# BluePill.net
KiCad netlist of a schematic drawn in Altium Designer
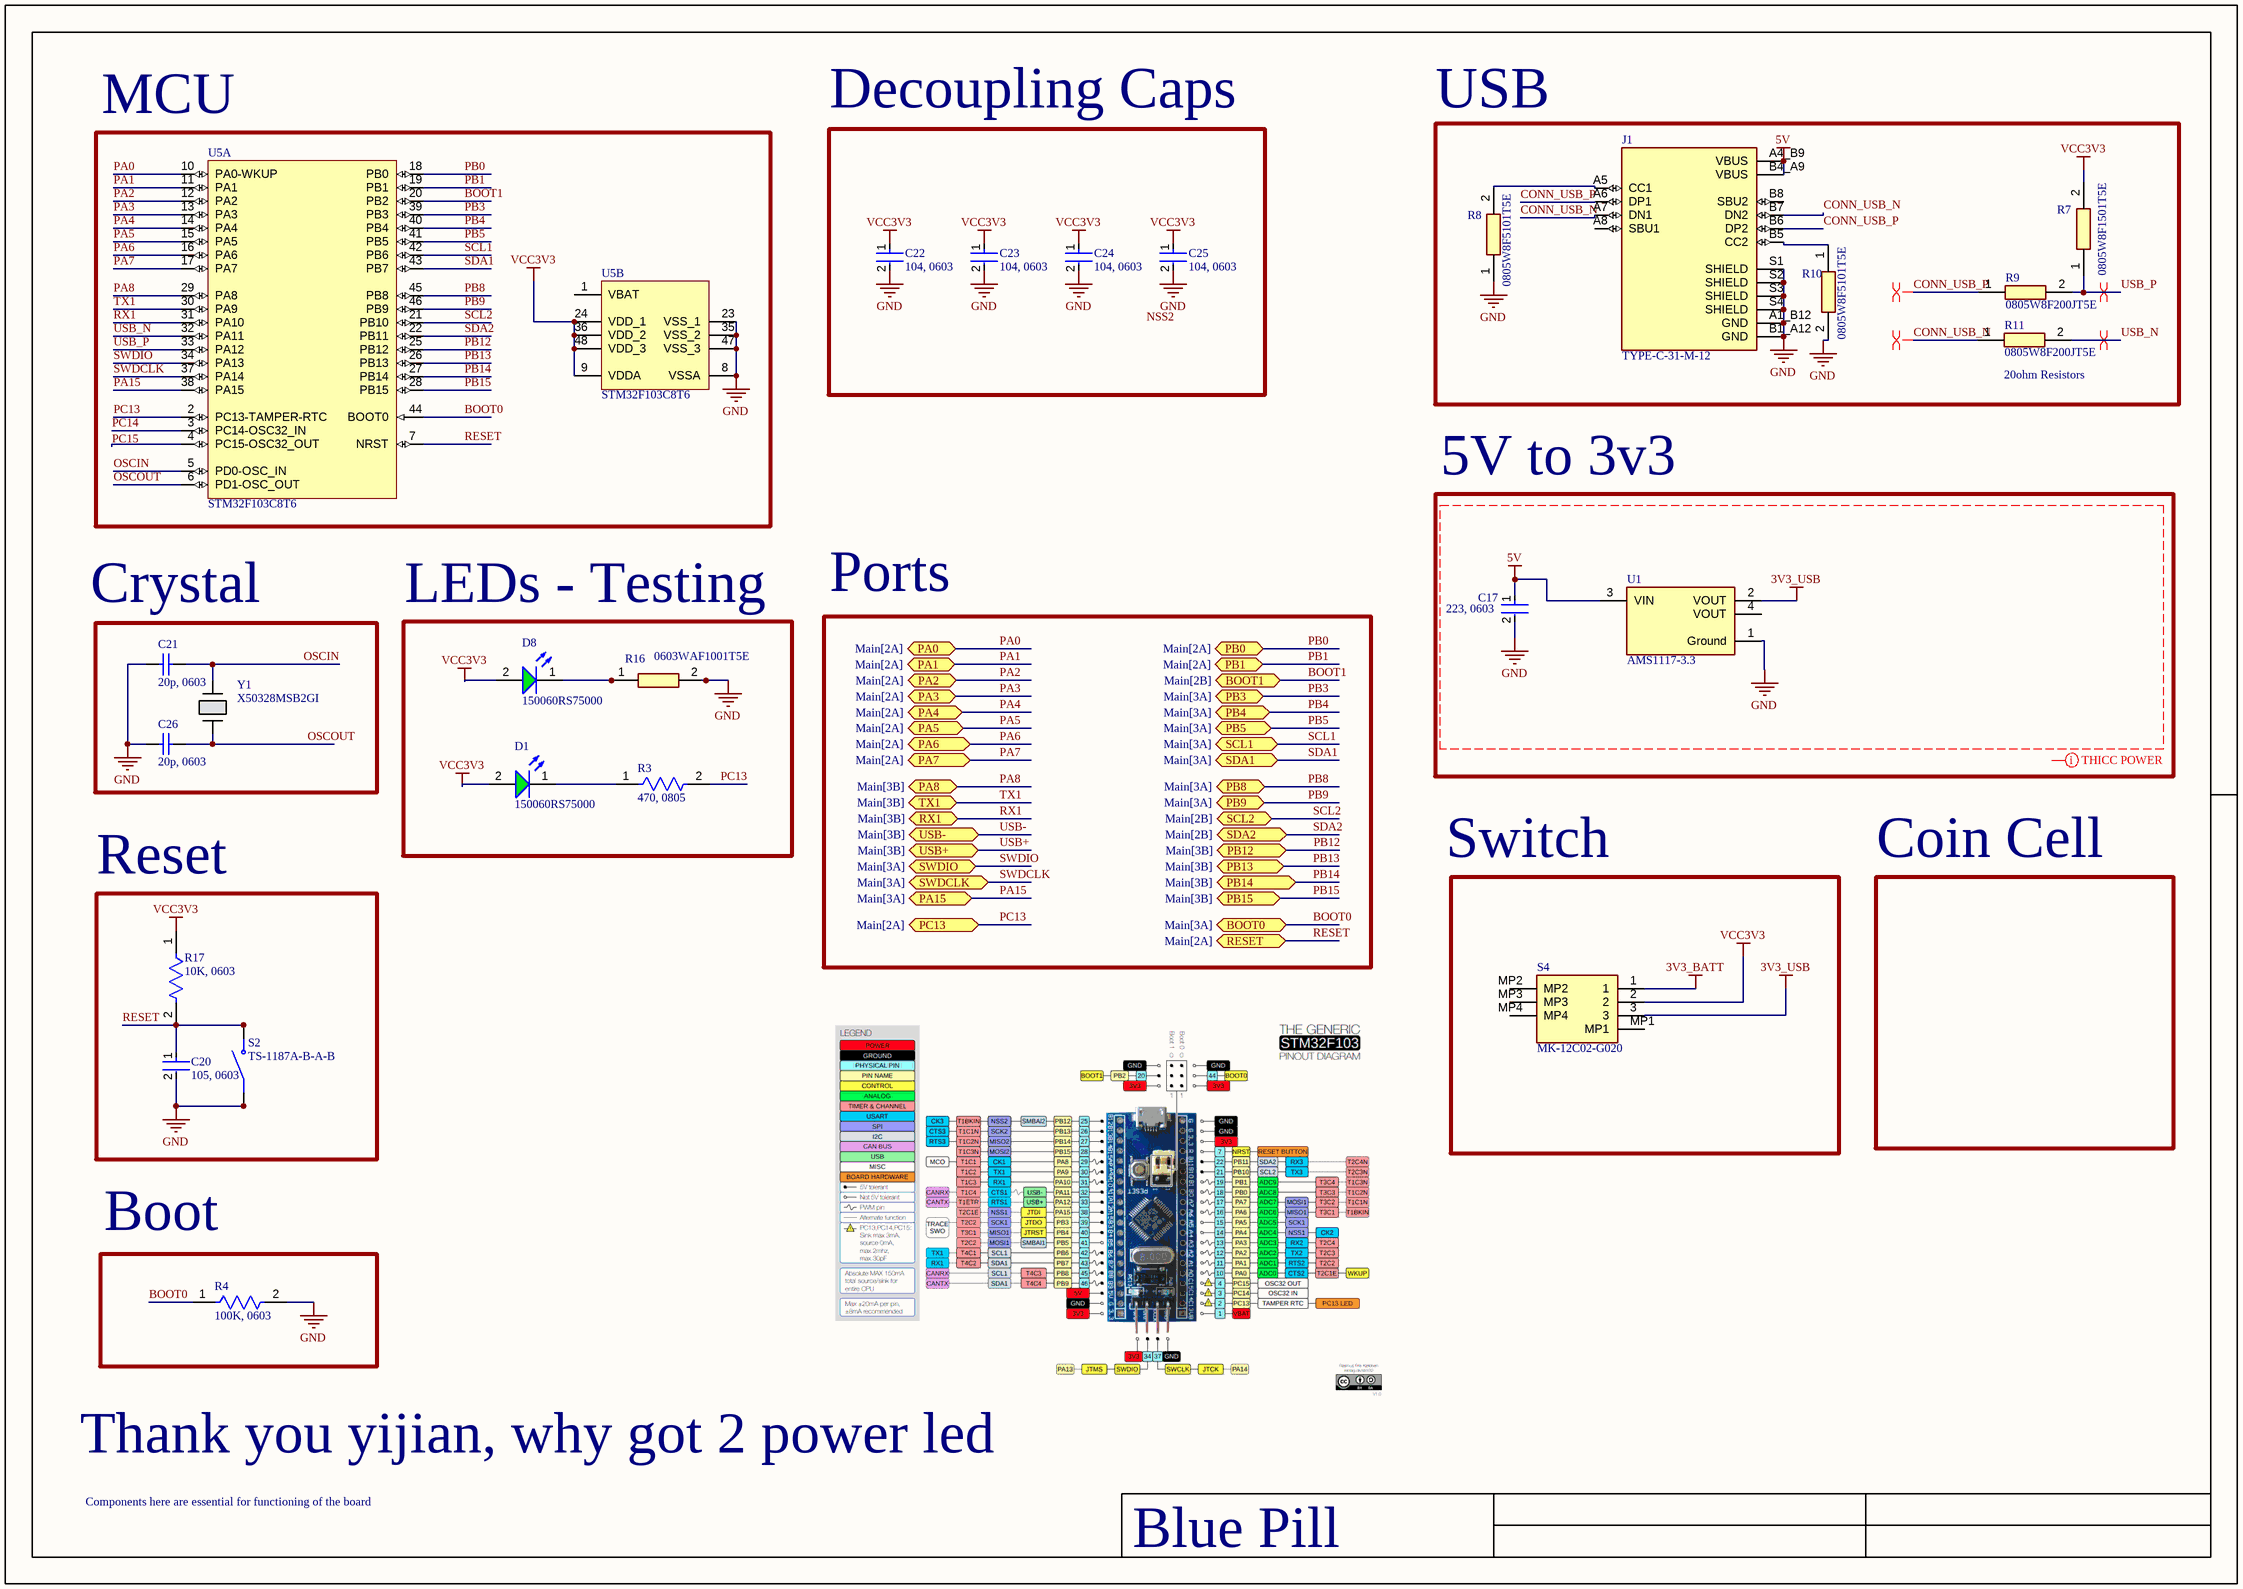
[diagram p0: BluePill.SchDoc]

(export (version "E")
  (design (tool "Eeschema 10.0.6"))
  (components
    (comp (ref "C17")
      (value "223, 0603")
      (footprint "FP-CC0603-DA-MFG")
      (description "CAP CER 0.022UF 50V X7R 0603")
      (fields (field (name "TOLERANCE") "10%") (field (name "VOLTAGE") "50V"))
      (libsource (lib "Altium Content Vault") (part "11868f565c42a9108669ba33697ecf6"))
    )
    (comp (ref "C20")
      (value "105, 0603")
      (footprint "FP-CC0603-DA-MFG")
      (description "CAP CER 1UF 16V X5R 0603")
      (fields
        (field (name "OCTOPART") "https://octopart.com/cc0603krx5r7bb105-yageo-8376530")
        (field (name "MANUFACTURER PART NUMBER") "CC0603KRX5R7BB105")
      )
      (libsource (lib "Altium Content Vault") (part "11868f565c42a9108669ba33697ecf6"))
    )
    (comp (ref "C21")
      (value "20p, 0603")
      (footprint "CAPC1608X90X30LL10T20")
      (description "Chip Capacitor, 20 pF, +/- 5%, 50 V, -55 to 85 degC, 0603 (1608 Metric), RoHS, Tape and Reel")
      (fields (field (name "MANUFACTURER") "Samsung Electro-Mechanics"))
      (libsource (lib "Altium Content Vault") (part "CAP-NP-2"))
    )
    (comp (ref "C22")
      (value "104, 0603")
      (footprint "FP-CC0603-DA-MFG")
      (description "CAP CER 0.1UF 16V X7R 0603")
      (fields
        (field (name "OCTOPART") "https://octopart.com/cc0603krx7r7bb104-yageo-192941")
        (field (name "TOLERANCE") "0.1")
      )
      (libsource (lib "Altium Content Vault") (part "11868f565c42a9108669ba33697ecf6"))
    )
    (comp (ref "C23")
      (value "104, 0603")
      (footprint "FP-CC0603-DA-MFG")
      (description "CAP CER 0.1UF 16V X7R 0603")
      (fields
        (field (name "OCTOPART") "https://octopart.com/cc0603krx7r7bb104-yageo-192941")
        (field (name "TOLERANCE") "0.1")
      )
      (libsource (lib "Altium Content Vault") (part "11868f565c42a9108669ba33697ecf6"))
    )
    (comp (ref "C24")
      (value "104, 0603")
      (footprint "FP-CC0603-DA-MFG")
      (description "CAP CER 0.1UF 16V X7R 0603")
      (fields
        (field (name "OCTOPART") "https://octopart.com/cc0603krx7r7bb104-yageo-192941")
        (field (name "TOLERANCE") "0.1")
      )
      (libsource (lib "Altium Content Vault") (part "11868f565c42a9108669ba33697ecf6"))
    )
    (comp (ref "C25")
      (value "104, 0603")
      (footprint "FP-CC0603-DA-MFG")
      (description "CAP CER 0.1UF 16V X7R 0603")
      (fields
        (field (name "OCTOPART") "https://octopart.com/cc0603krx7r7bb104-yageo-192941")
        (field (name "TOLERANCE") "0.1")
      )
      (libsource (lib "Altium Content Vault") (part "11868f565c42a9108669ba33697ecf6"))
    )
    (comp (ref "C26")
      (value "20p, 0603")
      (footprint "CAPC1608X90X30LL10T20")
      (description "Chip Capacitor, 20 pF, +/- 5%, 50 V, -55 to 85 degC, 0603 (1608 Metric), RoHS, Tape and Reel")
      (fields (field (name "MANUFACTURER") "Samsung Electro-Mechanics"))
      (libsource (lib "Altium Content Vault") (part "CAP-NP-2"))
    )
    (comp (ref "D1")
      (value "150060RS75000")
      (footprint "WL-SMCW_0805_150080xx75000")
      (libsource (lib "Altium Content Vault") (part "LED_Green_2A-1K"))
    )
    (comp (ref "D8")
      (value "150060RS75000")
      (footprint "WL-SMCW_0805_150080xx75000")
      (libsource (lib "Altium Content Vault") (part "LED_Green_2A-1K"))
    )
    (comp (ref "J1")
      (value "TYPE-C-31-M-12")
      (footprint "HRO_TYPE-C-31-M-12")
      (description "USB Connectors 24 Receptacle 1 8.94*7.3mm RoHS")
      (fields (field (name "MF") "HRO Electronics Co., Ltd."))
      (libsource (lib "Hackin7") (part "TYPE-C-31-M-12"))
    )
    (comp (ref "R3")
      (value "470, 0805")
      (footprint "FP-RT0805-MFG")
      (description "RES SMD 470 OHM 1% 1/8W 0805")
      (fields
        (field (name "TOLERANCE") "0.0001")
        (field (name "MANUFACTURER PART NUMBER") "RT0805FRE07470RL")
      )
      (libsource (lib "Altium Content Vault") (part "1029c3af85768c4190bb7ad29bc67b5"))
    )
    (comp (ref "R4")
      (value "100K, 0603")
      (footprint "FP-RT0603-MFG")
      (description "RES SMD 100K OHM 1% 1/10W 0603")
      (fields
        (field (name "TOLERANCE") "0.01")
        (field (name "OCTOPART") "https://octopart.com/rt0603fre07100kl-yageo-41455806")
      )
      (libsource (lib "Altium Content Vault") (part "1029c3af85768c4190bb7ad29bc67b5"))
    )
    (comp (ref "R7")
      (value "0805W8F1501T5E")
      (footprint "SamacSys:RESC2013X65N")
      (description "Resistor")
      (libsource (lib "") (part "0805W8F200JT5E_1"))
    )
    (comp (ref "R8")
      (value "0805W8F5101T5E")
      (footprint "SamacSys:RESC2013X65N")
      (description "Resistor")
      (libsource (lib "") (part "0805W8F5101T5E_1"))
    )
    (comp (ref "R9")
      (value "0805W8F200JT5E")
      (footprint "SamacSys:RESC2013X65N")
      (description "Resistor")
      (libsource (lib "*") (part "0805W8F200JT5E"))
    )
    (comp (ref "R10")
      (value "0805W8F5101T5E")
      (footprint "SamacSys:RESC2013X65N")
      (description "Resistor")
      (libsource (lib "*") (part "0805W8F5101T5E"))
    )
    (comp (ref "R11")
      (value "0805W8F200JT5E")
      (footprint "SamacSys:RESC2013X65N")
      (description "Resistor")
      (libsource (lib "*") (part "0805W8F200JT5E"))
    )
    (comp (ref "R16")
      (value "0603WAF1001T5E")
      (footprint "RESC1608X55N")
      (description "1k +/-1% 0.1W +/-100ppm/ 0603 Chip Resistor - Surface Mount")
      (libsource (lib "Hornet 9 Altium") (part "0603WAF1001T5E"))
    )
    (comp (ref "R17")
      (value "10K, 0603")
      (footprint "FP-RC0603-0_55-IPC_C")
      (description "RES 10K OHM 1% 1/10W 0603")
      (fields (field (name "TOLERANCE") "1%"))
      (libsource (lib "Altium Content Vault") (part "1029c3af85768c4190bb7ad29bc67b5"))
    )
    (comp (ref "S2")
      (value "TS-1187A-B-A-B")
      (footprint "SW_TS-1187A-B-A-B")
      (description "SPST 50mA @ 12VDC Top Actuated Round Button 160gf SMD Tactile Switches RoHS")
      (libsource (lib "Hornet 9 Altium") (part "TS-1187A-B-A-B"))
    )
    (comp (ref "S4")
      (value "MK-12C02-G020")
      (footprint "SamacSys:MK12C02G020")
      (description "Switch")
      (libsource (lib "*") (part "MK-12C02-G020"))
    )
    (comp (ref "U1")
      (value "AMS1117-3.3")
      (footprint "FP-AMS1117-IPC_B")
      (description "Fixed Positive LDO Regulator, 3.3V, 1.3V Dropout, PDSO3")
      (libsource (lib "Hackin7") (part "8bdbb5f8e77002000e30dd2845d0354"))
    )
    (comp (ref "U5")
      (value "STM32F103C8T6")
      (footprint "STM-LQFP48_L")
      (libsource (lib "Altium Content Vault") (part "MC-ARM-STM32F103X8_B-SQ48"))
    )
    (comp (ref "Y1")
      (value "X50328MSB2GI")
      (footprint "XTAL_MSB2GI_YXC")
      (description "8MHz 20pF ±10ppm ±50ppm SMD5032-2P Crystals ROHS")
      (fields (field (name "COPYRIGHT") "Copyright (C) 2024 Ultra Librarian. All rights reserved."))
      (libsource (lib "Hornet 9 Altium") (part "X50328MSB2GI"))
    )
  )
  (nets
    (net (code "1") (name "/BOOT0") (class "Default")
      (node (ref "R4") (pin "1") (pinfunction "1_1") (pintype "passive"))
      (node (ref "U5") (pin "44") (pinfunction "BOOT0_44") (pintype "input"))
    )
    (net (code "2") (name "/BOOT1") (class "Default")
      (node (ref "U5") (pin "20") (pinfunction "PB2_20") (pintype "bidirectional"))
    )
    (net (code "3") (name "/CONN_USB_N") (class "Default")
      (node (ref "J1") (pin "A7") (pinfunction "DN1_A7") (pintype "bidirectional"))
      (node (ref "J1") (pin "B7") (pinfunction "DN2_B7") (pintype "bidirectional"))
      (node (ref "R11") (pin "1") (pinfunction "1_1") (pintype "passive"))
    )
    (net (code "4") (name "/CONN_USB_P") (class "Default")
      (node (ref "J1") (pin "A6") (pinfunction "DP1_A6") (pintype "bidirectional"))
      (node (ref "J1") (pin "B6") (pinfunction "DP2_B6") (pintype "bidirectional"))
      (node (ref "R9") (pin "1") (pinfunction "1_1") (pintype "passive"))
    )
    (net (code "6") (name "/OSCIN") (class "Default")
      (node (ref "C21") (pin "2") (pinfunction "2_2") (pintype "passive"))
      (node (ref "U5") (pin "5") (pinfunction "PD0-OSC_IN_5") (pintype "bidirectional"))
      (node (ref "Y1") (pin "1") (pinfunction "1_1") (pintype "passive"))
    )
    (net (code "7") (name "/OSCOUT") (class "Default")
      (node (ref "C26") (pin "2") (pinfunction "2_2") (pintype "passive"))
      (node (ref "U5") (pin "6") (pinfunction "PD1-OSC_OUT_6") (pintype "bidirectional"))
      (node (ref "Y1") (pin "2") (pinfunction "2_2") (pintype "passive"))
    )
    (net (code "8") (name "/PA0") (class "Default")
      (node (ref "U5") (pin "10") (pinfunction "PA0-WKUP_10") (pintype "bidirectional"))
    )
    (net (code "9") (name "/PA1") (class "Default")
      (node (ref "U5") (pin "11") (pinfunction "PA1_11") (pintype "bidirectional"))
    )
    (net (code "10") (name "/PA2") (class "Default")
      (node (ref "U5") (pin "12") (pinfunction "PA2_12") (pintype "bidirectional"))
    )
    (net (code "11") (name "/PA3") (class "Default")
      (node (ref "U5") (pin "13") (pinfunction "PA3_13") (pintype "bidirectional"))
    )
    (net (code "12") (name "/PA4") (class "Default")
      (node (ref "U5") (pin "14") (pinfunction "PA4_14") (pintype "bidirectional"))
    )
    (net (code "13") (name "/PA5") (class "Default")
      (node (ref "U5") (pin "15") (pinfunction "PA5_15") (pintype "bidirectional"))
    )
    (net (code "14") (name "/PA6") (class "Default")
      (node (ref "U5") (pin "16") (pinfunction "PA6_16") (pintype "bidirectional"))
    )
    (net (code "15") (name "/PA7") (class "Default")
      (node (ref "U5") (pin "17") (pinfunction "PA7_17") (pintype "bidirectional"))
    )
    (net (code "16") (name "/PA8") (class "Default")
      (node (ref "U5") (pin "29") (pinfunction "PA8_29") (pintype "bidirectional"))
    )
    (net (code "17") (name "/PA15") (class "Default")
      (node (ref "U5") (pin "38") (pinfunction "PA15_38") (pintype "bidirectional"))
    )
    (net (code "18") (name "/PB0") (class "Default")
      (node (ref "U5") (pin "18") (pinfunction "PB0_18") (pintype "bidirectional"))
    )
    (net (code "19") (name "/PB1") (class "Default")
      (node (ref "U5") (pin "19") (pinfunction "PB1_19") (pintype "bidirectional"))
    )
    (net (code "20") (name "/PB3") (class "Default")
      (node (ref "U5") (pin "39") (pinfunction "PB3_39") (pintype "bidirectional"))
    )
    (net (code "21") (name "/PB4") (class "Default")
      (node (ref "U5") (pin "40") (pinfunction "PB4_40") (pintype "bidirectional"))
    )
    (net (code "22") (name "/PB5") (class "Default")
      (node (ref "U5") (pin "41") (pinfunction "PB5_41") (pintype "bidirectional"))
    )
    (net (code "23") (name "/PB8") (class "Default")
      (node (ref "U5") (pin "45") (pinfunction "PB8_45") (pintype "bidirectional"))
    )
    (net (code "24") (name "/PB9") (class "Default")
      (node (ref "U5") (pin "46") (pinfunction "PB9_46") (pintype "bidirectional"))
    )
    (net (code "25") (name "/PB12") (class "Default")
      (node (ref "U5") (pin "25") (pinfunction "PB12_25") (pintype "bidirectional"))
    )
    (net (code "26") (name "/PB13") (class "Default")
      (node (ref "U5") (pin "26") (pinfunction "PB13_26") (pintype "bidirectional"))
    )
    (net (code "27") (name "/PB14") (class "Default")
      (node (ref "U5") (pin "27") (pinfunction "PB14_27") (pintype "bidirectional"))
    )
    (net (code "28") (name "/PB15") (class "Default")
      (node (ref "U5") (pin "28") (pinfunction "PB15_28") (pintype "bidirectional"))
    )
    (net (code "29") (name "/PC13") (class "Default")
      (node (ref "R3") (pin "2") (pinfunction "2_2") (pintype "passive"))
      (node (ref "U5") (pin "2") (pinfunction "PC13-TAMPER-RTC_2") (pintype "bidirectional"))
    )
    (net (code "30") (name "/PC14") (class "Default")
      (node (ref "U5") (pin "3") (pinfunction "PC14-OSC32_IN_3") (pintype "bidirectional"))
    )
    (net (code "31") (name "/PC15") (class "Default")
      (node (ref "U5") (pin "4") (pinfunction "PC15-OSC32_OUT_4") (pintype "bidirectional"))
    )
    (net (code "32") (name "/RESET") (class "Default")
      (node (ref "C20") (pin "1") (pinfunction "1_1") (pintype "passive"))
      (node (ref "R17") (pin "2") (pinfunction "2_2") (pintype "passive"))
      (node (ref "S2") (pin "C") (pinfunction "NO_C") (pintype "passive"))
      (node (ref "S2") (pin "D") (pinfunction "NO_D") (pintype "passive"))
      (node (ref "U5") (pin "7") (pinfunction "NRST_7") (pintype "bidirectional"))
    )
    (net (code "33") (name "/RX1") (class "Default")
      (node (ref "U5") (pin "31") (pinfunction "PA10_31") (pintype "bidirectional"))
    )
    (net (code "34") (name "/SCL1") (class "Default")
      (node (ref "U5") (pin "42") (pinfunction "PB6_42") (pintype "bidirectional"))
    )
    (net (code "35") (name "/SCL2") (class "Default")
      (node (ref "U5") (pin "21") (pinfunction "PB10_21") (pintype "bidirectional"))
    )
    (net (code "36") (name "/SDA1") (class "Default")
      (node (ref "U5") (pin "43") (pinfunction "PB7_43") (pintype "bidirectional"))
    )
    (net (code "37") (name "/SDA2") (class "Default")
      (node (ref "U5") (pin "22") (pinfunction "PB11_22") (pintype "bidirectional"))
    )
    (net (code "38") (name "/SWDCLK") (class "Default")
      (node (ref "U5") (pin "37") (pinfunction "PA14_37") (pintype "bidirectional"))
    )
    (net (code "39") (name "/SWDIO") (class "Default")
      (node (ref "U5") (pin "34") (pinfunction "PA13_34") (pintype "bidirectional"))
    )
    (net (code "40") (name "/TX1") (class "Default")
      (node (ref "U5") (pin "30") (pinfunction "PA9_30") (pintype "bidirectional"))
    )
    (net (code "43") (name "/USB_N") (class "Default")
      (node (ref "R11") (pin "2") (pinfunction "2_2") (pintype "passive"))
      (node (ref "U5") (pin "32") (pinfunction "PA11_32") (pintype "bidirectional"))
    )
    (net (code "44") (name "/USB_P") (class "Default")
      (node (ref "R7") (pin "1") (pinfunction "1_1") (pintype "passive"))
      (node (ref "R9") (pin "2") (pinfunction "2_2") (pintype "passive"))
      (node (ref "U5") (pin "33") (pinfunction "PA12_33") (pintype "bidirectional"))
    )
    (net (code "45") (name "3V3_BATT") (class "Default")
      (node (ref "S4") (pin "1") (pinfunction "1_1") (pintype "passive"))
    )
    (net (code "46") (name "3V3_USB") (class "Default")
      (node (ref "S4") (pin "3") (pinfunction "3_3") (pintype "passive"))
      (node (ref "U1") (pin "2") (pinfunction "VOUT_2") (pintype "passive"))
    )
    (net (code "47") (name "5V") (class "Default")
      (node (ref "C17") (pin "1") (pinfunction "1_1") (pintype "passive"))
      (node (ref "J1") (pin "A4_B9") (pinfunction "VBUS_A4_B9") (pintype "power_in"))
      (node (ref "J1") (pin "B4_A9") (pinfunction "VBUS_B4_A9") (pintype "power_in"))
      (node (ref "U1") (pin "3") (pinfunction "VIN_3") (pintype "power_in"))
    )
    (net (code "48") (name "GND") (class "Default")
      (node (ref "C17") (pin "2") (pinfunction "2_2") (pintype "passive"))
      (node (ref "C20") (pin "2") (pinfunction "2_2") (pintype "passive"))
      (node (ref "C21") (pin "1") (pinfunction "1_1") (pintype "passive"))
      (node (ref "C22") (pin "2") (pinfunction "2_2") (pintype "passive"))
      (node (ref "C23") (pin "2") (pinfunction "2_2") (pintype "passive"))
      (node (ref "C24") (pin "2") (pinfunction "2_2") (pintype "passive"))
      (node (ref "C25") (pin "2") (pinfunction "2_2") (pintype "passive"))
      (node (ref "C26") (pin "1") (pinfunction "1_1") (pintype "passive"))
      (node (ref "J1") (pin "A1_B12") (pinfunction "GND_A1_B12") (pintype "power_in"))
      (node (ref "J1") (pin "B1_A12") (pinfunction "GND_B1_A12") (pintype "power_in"))
      (node (ref "J1") (pin "S1") (pinfunction "SHIELD_S1") (pintype "passive"))
      (node (ref "J1") (pin "S2") (pinfunction "SHIELD_S2") (pintype "passive"))
      (node (ref "J1") (pin "S3") (pinfunction "SHIELD_S3") (pintype "passive"))
      (node (ref "J1") (pin "S4") (pinfunction "SHIELD_S4") (pintype "passive"))
      (node (ref "R10") (pin "2") (pinfunction "2_2") (pintype "passive"))
      (node (ref "R16") (pin "2") (pinfunction "2_2") (pintype "passive"))
      (node (ref "R4") (pin "2") (pinfunction "2_2") (pintype "passive"))
      (node (ref "R8") (pin "1") (pinfunction "1_1") (pintype "passive"))
      (node (ref "S2") (pin "A") (pinfunction "COM_A") (pintype "passive"))
      (node (ref "S2") (pin "B") (pinfunction "COM_B") (pintype "passive"))
      (node (ref "U1") (pin "1") (pinfunction "Ground_1") (pintype "power_in"))
      (node (ref "U5") (pin "23") (pinfunction "VSS_1_23") (pintype "power_in"))
      (node (ref "U5") (pin "35") (pinfunction "VSS_2_35") (pintype "power_in"))
      (node (ref "U5") (pin "47") (pinfunction "VSS_3_47") (pintype "power_in"))
      (node (ref "U5") (pin "8") (pinfunction "VSSA_8") (pintype "power_in"))
    )
    (net (code "49") (name "Net-(D1-K)") (class "Default")
      (node (ref "D1") (pin "1") (pinfunction "K_1") (pintype "passive"))
      (node (ref "R3") (pin "1") (pinfunction "1_1") (pintype "passive"))
    )
    (net (code "50") (name "Net-(D8-K)") (class "Default")
      (node (ref "D8") (pin "1") (pinfunction "K_1") (pintype "passive"))
      (node (ref "R16") (pin "1") (pinfunction "1_1") (pintype "passive"))
    )
    (net (code "51") (name "Net-(J1-CC1)") (class "Default")
      (node (ref "J1") (pin "A5") (pinfunction "CC1_A5") (pintype "bidirectional"))
      (node (ref "R8") (pin "2") (pinfunction "2_2") (pintype "passive"))
    )
    (net (code "52") (name "Net-(J1-CC2)") (class "Default")
      (node (ref "J1") (pin "B5") (pinfunction "CC2_B5") (pintype "bidirectional"))
      (node (ref "R10") (pin "1") (pinfunction "1_1") (pintype "passive"))
    )
    (net (code "53") (name "VCC3V3") (class "Default")
      (node (ref "C22") (pin "1") (pinfunction "1_1") (pintype "passive"))
      (node (ref "C23") (pin "1") (pinfunction "1_1") (pintype "passive"))
      (node (ref "C24") (pin "1") (pinfunction "1_1") (pintype "passive"))
      (node (ref "C25") (pin "1") (pinfunction "1_1") (pintype "passive"))
      (node (ref "D1") (pin "2") (pinfunction "A_2") (pintype "passive"))
      (node (ref "D8") (pin "2") (pinfunction "A_2") (pintype "passive"))
      (node (ref "R17") (pin "1") (pinfunction "1_1") (pintype "passive"))
      (node (ref "R7") (pin "2") (pinfunction "2_2") (pintype "passive"))
      (node (ref "S4") (pin "2") (pinfunction "2_2") (pintype "passive"))
      (node (ref "U5") (pin "24") (pinfunction "VDD_1_24") (pintype "power_in"))
      (node (ref "U5") (pin "36") (pinfunction "VDD_2_36") (pintype "power_in"))
      (node (ref "U5") (pin "48") (pinfunction "VDD_3_48") (pintype "power_in"))
      (node (ref "U5") (pin "9") (pinfunction "VDDA_9") (pintype "power_in"))
    )
    (net (code "54") (name "unconnected-(J1-SBU1-PadA8)") (class "Default")
      (node (ref "J1") (pin "A8") (pinfunction "SBU1_A8") (pintype "bidirectional"))
    )
    (net (code "55") (name "unconnected-(J1-SBU2-PadB8)") (class "Default")
      (node (ref "J1") (pin "B8") (pinfunction "SBU2_B8") (pintype "bidirectional"))
    )
    (net (code "56") (name "unconnected-(S4-PadMP1)") (class "Default")
      (node (ref "S4") (pin "MP1") (pinfunction "MP1_MP1") (pintype "passive"))
    )
    (net (code "57") (name "unconnected-(S4-PadMP2)") (class "Default")
      (node (ref "S4") (pin "MP2") (pinfunction "MP2_MP2") (pintype "passive"))
    )
    (net (code "58") (name "unconnected-(S4-PadMP3)") (class "Default")
      (node (ref "S4") (pin "MP3") (pinfunction "MP3_MP3") (pintype "passive"))
    )
    (net (code "59") (name "unconnected-(S4-PadMP4)") (class "Default")
      (node (ref "S4") (pin "MP4") (pinfunction "MP4_MP4") (pintype "passive"))
    )
    (net (code "60") (name "unconnected-(U1-VOUT-Pad4)") (class "Default")
      (node (ref "U1") (pin "4") (pinfunction "VOUT_4") (pintype "passive"))
    )
    (net (code "61") (name "unconnected-(U5B-VBAT-Pad1)") (class "Default")
      (node (ref "U5") (pin "1") (pinfunction "VBAT_1") (pintype "power_in"))
    )
  )
)
